# P6_ESTACIONMETEOROLOGICA.net
KiCad netlist of a schematic drawn in EAGLE
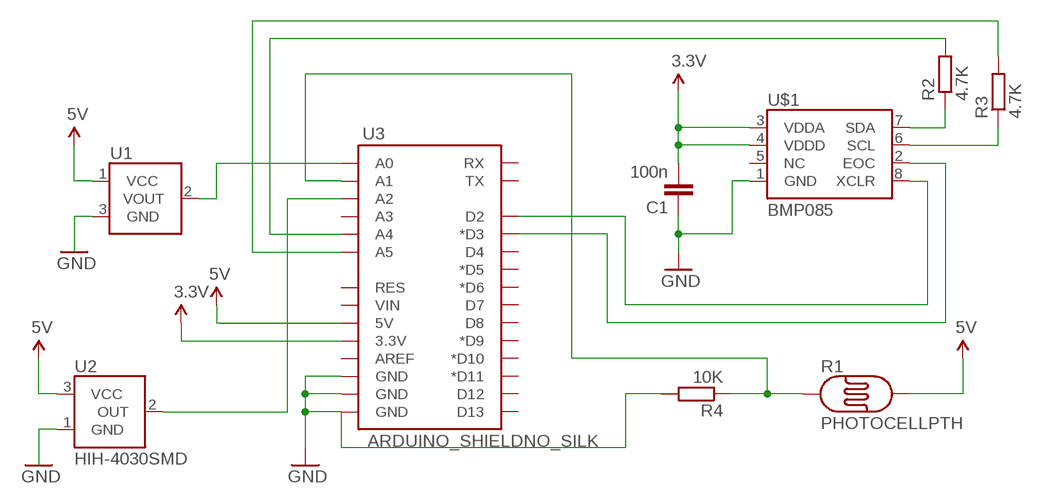
[diagram p0: schematic, sheet 1]

(export (version "E")
  (design (tool "Eeschema 10.0.6"))
  (components
    (comp (ref "C1")
      (value "100n")
      (footprint "eagle-import:C0805")
      (libsource (lib "eagle-import") (part "C"))
    )
    (comp (ref "R1")
      (value "PHOTOCELLPTH")
      (footprint "eagle-import:PHOTOCELL")
      (libsource (lib "eagle-import") (part "PHOTOCELLPTH"))
    )
    (comp (ref "R2")
      (value "4.7K")
      (footprint "eagle-import:R0805")
      (libsource (lib "eagle-import") (part "R"))
    )
    (comp (ref "R3")
      (value "4.7K")
      (footprint "eagle-import:R0805")
      (libsource (lib "eagle-import") (part "R"))
    )
    (comp (ref "R4")
      (value "10K")
      (footprint "eagle-import:R0805")
      (libsource (lib "eagle-import") (part "R"))
    )
    (comp (ref "U$1")
      (value "BMP085")
      (footprint "eagle-import:BMP085")
      (libsource (lib "eagle-import") (part "BMP085"))
    )
    (comp (ref "U1")
      (value "TMP36GT9")
      (footprint "eagle-import:TO-92")
      (libsource (lib "eagle-import") (part "TMP36GT9"))
    )
    (comp (ref "U2")
      (value "HIH-4030SMD")
      (footprint "eagle-import:HIH-4030")
      (libsource (lib "eagle-import") (part "HIH-4030SMD"))
    )
    (comp (ref "U3")
      (value "ARDUINO_SHIELDNO_SILK")
      (footprint "eagle-import:DUEMILANOVE_VIAS")
      (libsource (lib "eagle-import") (part "ARDUINO_SHIELDNO_SILK"))
    )
  )
  (nets
    (net (code "1") (name "3.3V") (class "Default")
      (node (ref "C1") (pin "2") (pinfunction "2_2") (pintype "passive"))
      (node (ref "U$1") (pin "3") (pinfunction "VDDA_3") (pintype "power_in"))
      (node (ref "U$1") (pin "4") (pinfunction "VDDD_4") (pintype "power_in"))
      (node (ref "U3") (pin "3.3V") (pinfunction "3.3V_3.3V") (pintype "bidirectional"))
    )
    (net (code "2") (name "5V") (class "Default")
      (node (ref "R1") (pin "2") (pinfunction "P$2_2") (pintype "bidirectional"))
      (node (ref "U1") (pin "1") (pinfunction "VCC_1") (pintype "bidirectional"))
      (node (ref "U2") (pin "3") (pinfunction "VCC_3") (pintype "bidirectional"))
      (node (ref "U3") (pin "5V") (pinfunction "5V_5V") (pintype "bidirectional"))
    )
    (net (code "3") (name "GND") (class "Default")
      (node (ref "C1") (pin "1") (pinfunction "1_1") (pintype "passive"))
      (node (ref "U$1") (pin "1") (pinfunction "GND_1") (pintype "power_in"))
      (node (ref "U3") (pin "GND@0") (pinfunction "GND_GND@0") (pintype "bidirectional"))
      (node (ref "U3") (pin "GND@1") (pinfunction "GND_GND@1") (pintype "bidirectional"))
      (node (ref "U3") (pin "GND@2") (pinfunction "GND_GND@2") (pintype "bidirectional"))
    )
    (net (code "4") (name "Net-(R1-P$1)") (class "Default")
      (node (ref "R1") (pin "1") (pinfunction "P$1_1") (pintype "bidirectional"))
      (node (ref "R4") (pin "1") (pinfunction "1_1") (pintype "passive"))
      (node (ref "U3") (pin "A1") (pinfunction "A1_A1") (pintype "bidirectional"))
    )
    (net (code "5") (name "Net-(R2-Pad2)") (class "Default")
      (node (ref "R2") (pin "2") (pinfunction "2_2") (pintype "passive"))
      (node (ref "U3") (pin "A4") (pinfunction "A4_A4") (pintype "bidirectional"))
    )
    (net (code "6") (name "Net-(R3-Pad2)") (class "Default")
      (node (ref "R3") (pin "2") (pinfunction "2_2") (pintype "passive"))
      (node (ref "U3") (pin "A5") (pinfunction "A5_A5") (pintype "bidirectional"))
    )
    (net (code "7") (name "Net-(U$1-EOC)") (class "Default")
      (node (ref "U$1") (pin "2") (pinfunction "EOC_2") (pintype "output"))
      (node (ref "U3") (pin "D3") (pinfunction "*D3_D3") (pintype "bidirectional"))
    )
    (net (code "8") (name "Net-(U$1-SCL)") (class "Default")
      (node (ref "R3") (pin "1") (pinfunction "1_1") (pintype "passive"))
      (node (ref "U$1") (pin "6") (pinfunction "SCL_6") (pintype "input"))
    )
    (net (code "9") (name "Net-(U$1-SDA)") (class "Default")
      (node (ref "R2") (pin "1") (pinfunction "1_1") (pintype "passive"))
      (node (ref "U$1") (pin "7") (pinfunction "SDA_7") (pintype "bidirectional"))
    )
    (net (code "10") (name "Net-(U$1-XCLR)") (class "Default")
      (node (ref "U$1") (pin "8") (pinfunction "XCLR_8") (pintype "input"))
      (node (ref "U3") (pin "D2") (pinfunction "D2_D2") (pintype "bidirectional"))
    )
    (net (code "11") (name "Net-(U1-VOUT)") (class "Default")
      (node (ref "U1") (pin "2") (pinfunction "VOUT_2") (pintype "bidirectional"))
      (node (ref "U3") (pin "A0") (pinfunction "A0_A0") (pintype "bidirectional"))
    )
    (net (code "12") (name "Net-(U2-OUT)") (class "Default")
      (node (ref "U2") (pin "2") (pinfunction "OUT_2") (pintype "bidirectional"))
      (node (ref "U3") (pin "A2") (pinfunction "A2_A2") (pintype "bidirectional"))
    )
    (net (code "13") (name "unconnected-(R4-Pad2)") (class "Default")
      (node (ref "R4") (pin "2") (pinfunction "2_2") (pintype "passive"))
    )
    (net (code "14") (name "unconnected-(U$1-NC-Pad5)") (class "Default")
      (node (ref "U$1") (pin "5") (pinfunction "NC_5") (pintype "bidirectional"))
    )
    (net (code "15") (name "unconnected-(U1-GND-Pad3)") (class "Default")
      (node (ref "U1") (pin "3") (pinfunction "GND_3") (pintype "bidirectional"))
    )
    (net (code "16") (name "unconnected-(U2-GND-Pad1)") (class "Default")
      (node (ref "U2") (pin "1") (pinfunction "GND_1") (pintype "bidirectional"))
    )
    (net (code "17") (name "unconnected-(U3-*D5-PadD5)") (class "Default")
      (node (ref "U3") (pin "D5") (pinfunction "*D5_D5") (pintype "bidirectional"))
    )
    (net (code "18") (name "unconnected-(U3-*D6-PadD6)") (class "Default")
      (node (ref "U3") (pin "D6") (pinfunction "*D6_D6") (pintype "bidirectional"))
    )
    (net (code "19") (name "unconnected-(U3-*D9-PadD9)") (class "Default")
      (node (ref "U3") (pin "D9") (pinfunction "*D9_D9") (pintype "bidirectional"))
    )
    (net (code "20") (name "unconnected-(U3-*D10-PadD10)") (class "Default")
      (node (ref "U3") (pin "D10") (pinfunction "*D10_D10") (pintype "bidirectional"))
    )
    (net (code "21") (name "unconnected-(U3-*D11-PadD11)") (class "Default")
      (node (ref "U3") (pin "D11") (pinfunction "*D11_D11") (pintype "bidirectional"))
    )
    (net (code "22") (name "unconnected-(U3-PadA3)") (class "Default")
      (node (ref "U3") (pin "A3") (pinfunction "A3_A3") (pintype "bidirectional"))
    )
    (net (code "23") (name "unconnected-(U3-PadAREF)") (class "Default")
      (node (ref "U3") (pin "AREF") (pinfunction "AREF_AREF") (pintype "bidirectional"))
    )
    (net (code "24") (name "unconnected-(U3-PadD4)") (class "Default")
      (node (ref "U3") (pin "D4") (pinfunction "D4_D4") (pintype "bidirectional"))
    )
    (net (code "25") (name "unconnected-(U3-PadD7)") (class "Default")
      (node (ref "U3") (pin "D7") (pinfunction "D7_D7") (pintype "bidirectional"))
    )
    (net (code "26") (name "unconnected-(U3-PadD8)") (class "Default")
      (node (ref "U3") (pin "D8") (pinfunction "D8_D8") (pintype "bidirectional"))
    )
    (net (code "27") (name "unconnected-(U3-PadD12)") (class "Default")
      (node (ref "U3") (pin "D12") (pinfunction "D12_D12") (pintype "bidirectional"))
    )
    (net (code "28") (name "unconnected-(U3-PadD13)") (class "Default")
      (node (ref "U3") (pin "D13") (pinfunction "D13_D13") (pintype "bidirectional"))
    )
    (net (code "29") (name "unconnected-(U3-PadRES)") (class "Default")
      (node (ref "U3") (pin "RES") (pinfunction "RES_RES") (pintype "bidirectional"))
    )
    (net (code "30") (name "unconnected-(U3-PadRX)") (class "Default")
      (node (ref "U3") (pin "RX") (pinfunction "RX_RX") (pintype "bidirectional"))
    )
    (net (code "31") (name "unconnected-(U3-PadTX)") (class "Default")
      (node (ref "U3") (pin "TX") (pinfunction "TX_TX") (pintype "bidirectional"))
    )
    (net (code "32") (name "unconnected-(U3-PadVIN)") (class "Default")
      (node (ref "U3") (pin "VIN") (pinfunction "VIN_VIN") (pintype "bidirectional"))
    )
  )
)
